# RADC-ModuleConnect-S07-V00.net
KiCad netlist of a schematic drawn in Altium Designer
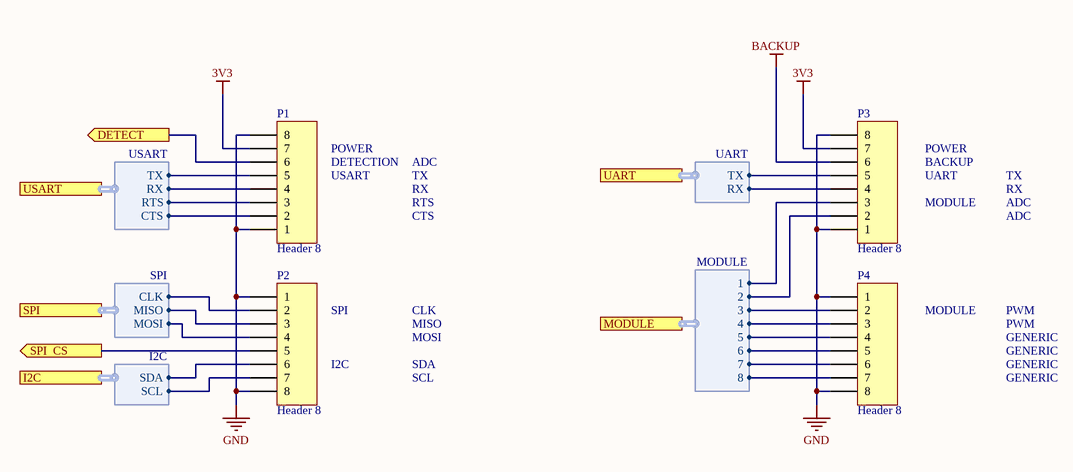
[diagram p0: RADC-ModuleConnect-S07-V00.SchDoc]

(export (version "E")
  (design (tool "Eeschema 10.0.6"))
  (components
    (comp (ref "P1")
      (value "Header 8")
      (footprint "HDR1X8")
      (description "Header, 8-Pin")
      (fields (field (name "PUBLISHER") "Altium Limited"))
      (libsource (lib "") (part "Header 8_1"))
    )
    (comp (ref "P2")
      (value "Header 8")
      (footprint "HDR1X8")
      (description "Header, 8-Pin")
      (fields (field (name "PUBLISHER") "Altium Limited"))
      (libsource (lib "Miscellaneous Connectors") (part "Header 8"))
    )
    (comp (ref "P3")
      (value "Header 8")
      (footprint "HDR1X8")
      (description "Header, 8-Pin")
      (fields (field (name "PUBLISHER") "Altium Limited"))
      (libsource (lib "") (part "Header 8_1"))
    )
    (comp (ref "P4")
      (value "Header 8")
      (footprint "HDR1X8")
      (description "Header, 8-Pin")
      (fields (field (name "PUBLISHER") "Altium Limited"))
      (libsource (lib "Miscellaneous Connectors") (part "Header 8"))
    )
  )
  (nets
    (net (code "6") (name "/1") (class "Default")
      (node (ref "P3") (pin "3") (pinfunction "3_3") (pintype "passive"))
    )
    (net (code "7") (name "/2") (class "Default")
      (node (ref "P3") (pin "2") (pinfunction "2_2") (pintype "passive"))
    )
    (net (code "8") (name "/3") (class "Default")
      (node (ref "P4") (pin "2") (pinfunction "2_2") (pintype "passive"))
    )
    (net (code "9") (name "/4") (class "Default")
      (node (ref "P4") (pin "3") (pinfunction "3_3") (pintype "passive"))
    )
    (net (code "10") (name "/5") (class "Default")
      (node (ref "P4") (pin "4") (pinfunction "4_4") (pintype "passive"))
    )
    (net (code "11") (name "/6") (class "Default")
      (node (ref "P4") (pin "5") (pinfunction "5_5") (pintype "passive"))
    )
    (net (code "12") (name "/7") (class "Default")
      (node (ref "P4") (pin "6") (pinfunction "6_6") (pintype "passive"))
    )
    (net (code "13") (name "/8") (class "Default")
      (node (ref "P4") (pin "7") (pinfunction "7_7") (pintype "passive"))
    )
    (net (code "14") (name "/CLK") (class "Default")
      (node (ref "P2") (pin "2") (pinfunction "2_2") (pintype "passive"))
    )
    (net (code "15") (name "/CTS") (class "Default")
      (node (ref "P1") (pin "2") (pinfunction "2_2") (pintype "passive"))
    )
    (net (code "16") (name "/DETECT") (class "Default")
      (node (ref "P1") (pin "6") (pinfunction "6_6") (pintype "passive"))
    )
    (net (code "17") (name "/MISO") (class "Default")
      (node (ref "P2") (pin "3") (pinfunction "3_3") (pintype "passive"))
    )
    (net (code "18") (name "/MOSI") (class "Default")
      (node (ref "P2") (pin "4") (pinfunction "4_4") (pintype "passive"))
    )
    (net (code "19") (name "/RTS") (class "Default")
      (node (ref "P1") (pin "3") (pinfunction "3_3") (pintype "passive"))
    )
    (net (code "20") (name "/SCL") (class "Default")
      (node (ref "P2") (pin "7") (pinfunction "7_7") (pintype "passive"))
    )
    (net (code "21") (name "/SDA") (class "Default")
      (node (ref "P2") (pin "6") (pinfunction "6_6") (pintype "passive"))
    )
    (net (code "22") (name "/SPI  CS") (class "Default")
      (node (ref "P2") (pin "5") (pinfunction "5_5") (pintype "passive"))
    )
    (net (code "28") (name "3V3") (class "Default")
      (node (ref "P1") (pin "7") (pinfunction "7_7") (pintype "passive"))
      (node (ref "P3") (pin "7") (pinfunction "7_7") (pintype "passive"))
    )
    (net (code "29") (name "BACKUP") (class "Default")
      (node (ref "P3") (pin "6") (pinfunction "6_6") (pintype "passive"))
    )
    (net (code "30") (name "GND") (class "Default")
      (node (ref "P1") (pin "1") (pinfunction "1_1") (pintype "passive"))
      (node (ref "P1") (pin "8") (pinfunction "8_8") (pintype "passive"))
      (node (ref "P2") (pin "1") (pinfunction "1_1") (pintype "passive"))
      (node (ref "P2") (pin "8") (pinfunction "8_8") (pintype "passive"))
      (node (ref "P3") (pin "1") (pinfunction "1_1") (pintype "passive"))
      (node (ref "P3") (pin "8") (pinfunction "8_8") (pintype "passive"))
      (node (ref "P4") (pin "1") (pinfunction "1_1") (pintype "passive"))
      (node (ref "P4") (pin "8") (pinfunction "8_8") (pintype "passive"))
    )
    (net (code "31") (name "unconnected-(P1-Pad4)") (class "Default")
      (node (ref "P1") (pin "4") (pinfunction "4_4") (pintype "passive"))
    )
    (net (code "32") (name "unconnected-(P1-Pad5)") (class "Default")
      (node (ref "P1") (pin "5") (pinfunction "5_5") (pintype "passive"))
    )
    (net (code "33") (name "unconnected-(P3-Pad4)") (class "Default")
      (node (ref "P3") (pin "4") (pinfunction "4_4") (pintype "passive"))
    )
    (net (code "34") (name "unconnected-(P3-Pad5)") (class "Default")
      (node (ref "P3") (pin "5") (pinfunction "5_5") (pintype "passive"))
    )
  )
)
